# relay-monostable-multivib.net
KiCad netlist of a schematic drawn in EAGLE
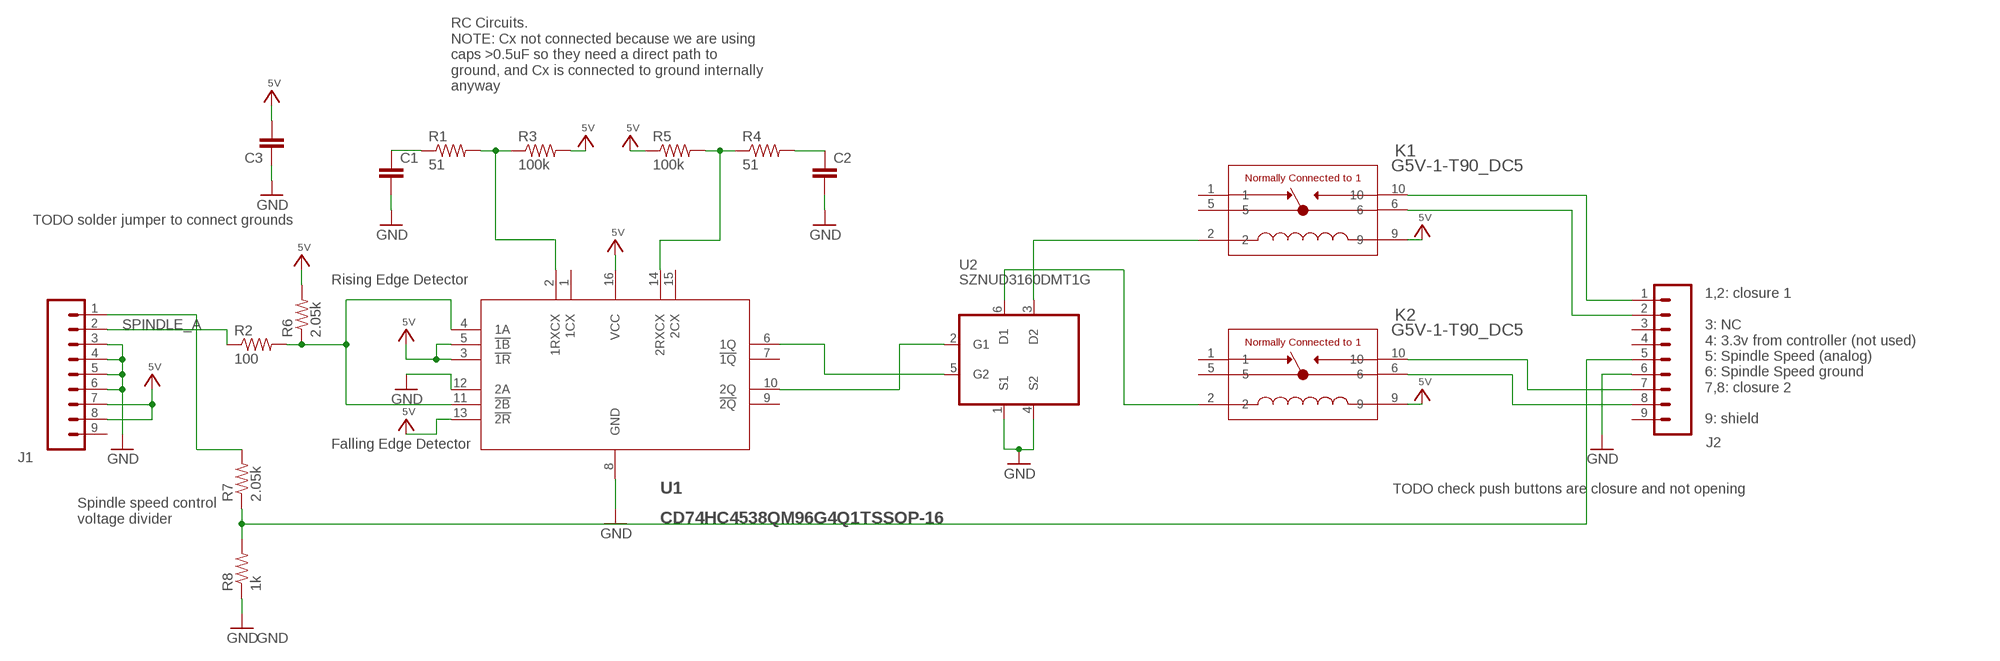
[diagram p0: schematic, sheet 1]

(export (version "E")
  (design (tool "Eeschema 10.0.6"))
  (components
    (comp (ref "C1")
      (value "C-EU1206-A")
      (footprint "eagle-import:1206-A")
      (libsource (lib "eagle-import") (part "C-EU1206-A"))
    )
    (comp (ref "C2")
      (value "C-EU1206-A")
      (footprint "eagle-import:1206-A")
      (libsource (lib "eagle-import") (part "C-EU1206-A"))
    )
    (comp (ref "C3")
      (value "C-EU1206-A")
      (footprint "eagle-import:1206-A")
      (libsource (lib "eagle-import") (part "C-EU1206-A"))
    )
    (comp (ref "J1")
      (value "CONN_09LONGPADS")
      (footprint "eagle-import:1X09_LONGPADS")
      (libsource (lib "eagle-import") (part "CONN_09LONGPADS"))
    )
    (comp (ref "J2")
      (value "CONN_09LONGPADS")
      (footprint "eagle-import:1X09_LONGPADS")
      (libsource (lib "eagle-import") (part "CONN_09LONGPADS"))
    )
    (comp (ref "K1")
      (value "G5V-1-T90_DC5")
      (footprint "eagle-import:RELAY_G5V-1_OMR")
      (fields
        (field (name "MANUFACTURER_PART_NUMBER") "G5V-1-T90 DC5")
        (field (name "COPYRIGHT") "Copyright (C) 2018 Accelerated Designs. All rights reserved")
      )
      (libsource (lib "eagle-import") (part "G5V-1-T90_DC5"))
    )
    (comp (ref "K2")
      (value "G5V-1-T90_DC5")
      (footprint "eagle-import:RELAY_G5V-1_OMR")
      (fields
        (field (name "MANUFACTURER_PART_NUMBER") "G5V-1-T90 DC5")
        (field (name "COPYRIGHT") "Copyright (C) 2018 Accelerated Designs. All rights reserved")
      )
      (libsource (lib "eagle-import") (part "G5V-1-T90_DC5"))
    )
    (comp (ref "R1")
      (value "51")
      (footprint "eagle-import:1206-A")
      (libsource (lib "eagle-import") (part "R-US_1206-A"))
    )
    (comp (ref "R2")
      (value "100")
      (footprint "eagle-import:1206-A")
      (libsource (lib "eagle-import") (part "R-US_1206-A"))
    )
    (comp (ref "R3")
      (value "100k")
      (footprint "eagle-import:1206-A")
      (libsource (lib "eagle-import") (part "R-US_1206-A"))
    )
    (comp (ref "R4")
      (value "51")
      (footprint "eagle-import:1206-A")
      (libsource (lib "eagle-import") (part "R-US_1206-A"))
    )
    (comp (ref "R5")
      (value "100k")
      (footprint "eagle-import:1206-A")
      (libsource (lib "eagle-import") (part "R-US_1206-A"))
    )
    (comp (ref "R6")
      (value "2.05k")
      (footprint "eagle-import:1206-A")
      (libsource (lib "eagle-import") (part "R-US_1206-A"))
    )
    (comp (ref "R7")
      (value "2.05k")
      (footprint "eagle-import:1206-A")
      (libsource (lib "eagle-import") (part "R-US_1206-A"))
    )
    (comp (ref "R8")
      (value "1k")
      (footprint "eagle-import:1206-A")
      (libsource (lib "eagle-import") (part "R-US_1206-A"))
    )
    (comp (ref "U1")
      (value "CD74HC4538QM96G4Q1TSSOP-16")
      (footprint "eagle-import:TSSOP16")
      (libsource (lib "eagle-import") (part "CD74HC4538QM96G4Q1TSSOP-16"))
    )
    (comp (ref "U2")
      (value "SZNUD3160DMT1G")
      (footprint "eagle-import:SC74_6")
      (libsource (lib "eagle-import") (part "SZNUD3160DMT1G"))
    )
  )
  (nets
    (net (code "1") (name "/SPINDLE_A") (class "Default")
      (node (ref "J1") (pin "1") (pinfunction "1_1") (pintype "passive"))
      (node (ref "R7") (pin "2") (pinfunction "2_2") (pintype "passive"))
    )
    (net (code "2") (name "5V") (class "Default")
      (node (ref "C3") (pin "2") (pinfunction "2_2") (pintype "passive"))
      (node (ref "J1") (pin "7") (pinfunction "7_7") (pintype "passive"))
      (node (ref "J1") (pin "8") (pinfunction "8_8") (pintype "passive"))
      (node (ref "K1") (pin "9") (pinfunction "9_9") (pintype "passive"))
      (node (ref "K2") (pin "9") (pinfunction "9_9") (pintype "passive"))
      (node (ref "R3") (pin "2") (pinfunction "2_2") (pintype "passive"))
      (node (ref "R5") (pin "1") (pinfunction "1_1") (pintype "passive"))
      (node (ref "R6") (pin "2") (pinfunction "2_2") (pintype "passive"))
      (node (ref "U1") (pin "13") (pinfunction "~{2R}_13") (pintype "input"))
      (node (ref "U1") (pin "16") (pinfunction "VCC_16") (pintype "power_in"))
      (node (ref "U1") (pin "3") (pinfunction "~{1R}_3") (pintype "input"))
      (node (ref "U1") (pin "5") (pinfunction "~{1B}_5") (pintype "input"))
    )
    (net (code "3") (name "GND") (class "Default")
      (node (ref "C1") (pin "2") (pinfunction "2_2") (pintype "passive"))
      (node (ref "C2") (pin "2") (pinfunction "2_2") (pintype "passive"))
      (node (ref "C3") (pin "1") (pinfunction "1_1") (pintype "passive"))
      (node (ref "J1") (pin "3") (pinfunction "3_3") (pintype "passive"))
      (node (ref "J1") (pin "4") (pinfunction "4_4") (pintype "passive"))
      (node (ref "J1") (pin "5") (pinfunction "5_5") (pintype "passive"))
      (node (ref "J1") (pin "6") (pinfunction "6_6") (pintype "passive"))
      (node (ref "J2") (pin "6") (pinfunction "6_6") (pintype "passive"))
      (node (ref "R8") (pin "1") (pinfunction "1_1") (pintype "passive"))
      (node (ref "U1") (pin "12") (pinfunction "2A_12") (pintype "input"))
      (node (ref "U1") (pin "8") (pinfunction "GND_8") (pintype "power_in"))
      (node (ref "U2") (pin "1") (pinfunction "S1_1") (pintype "power_in"))
      (node (ref "U2") (pin "4") (pinfunction "S2_4") (pintype "input"))
    )
    (net (code "4") (name "Net-(C1-Pad1)") (class "Default")
      (node (ref "C1") (pin "1") (pinfunction "1_1") (pintype "passive"))
      (node (ref "R1") (pin "1") (pinfunction "1_1") (pintype "passive"))
    )
    (net (code "5") (name "Net-(C2-Pad1)") (class "Default")
      (node (ref "C2") (pin "1") (pinfunction "1_1") (pintype "passive"))
      (node (ref "R4") (pin "2") (pinfunction "2_2") (pintype "passive"))
    )
    (net (code "6") (name "Net-(J1-Pad2)") (class "Default")
      (node (ref "J1") (pin "2") (pinfunction "2_2") (pintype "passive"))
      (node (ref "R2") (pin "1") (pinfunction "1_1") (pintype "passive"))
    )
    (net (code "7") (name "Net-(J2-Pad1)") (class "Default")
      (node (ref "J2") (pin "1") (pinfunction "1_1") (pintype "passive"))
      (node (ref "K1") (pin "10") (pinfunction "10_10") (pintype "passive"))
    )
    (net (code "8") (name "Net-(J2-Pad2)") (class "Default")
      (node (ref "J2") (pin "2") (pinfunction "2_2") (pintype "passive"))
      (node (ref "K1") (pin "6") (pinfunction "6_6") (pintype "passive"))
    )
    (net (code "9") (name "Net-(J2-Pad5)") (class "Default")
      (node (ref "J2") (pin "5") (pinfunction "5_5") (pintype "passive"))
      (node (ref "R7") (pin "1") (pinfunction "1_1") (pintype "passive"))
      (node (ref "R8") (pin "2") (pinfunction "2_2") (pintype "passive"))
    )
    (net (code "10") (name "Net-(J2-Pad7)") (class "Default")
      (node (ref "J2") (pin "7") (pinfunction "7_7") (pintype "passive"))
      (node (ref "K2") (pin "10") (pinfunction "10_10") (pintype "passive"))
    )
    (net (code "11") (name "Net-(J2-Pad8)") (class "Default")
      (node (ref "J2") (pin "8") (pinfunction "8_8") (pintype "passive"))
      (node (ref "K2") (pin "6") (pinfunction "6_6") (pintype "passive"))
    )
    (net (code "12") (name "Net-(U1-1A)") (class "Default")
      (node (ref "R2") (pin "2") (pinfunction "2_2") (pintype "passive"))
      (node (ref "R6") (pin "1") (pinfunction "1_1") (pintype "passive"))
      (node (ref "U1") (pin "11") (pinfunction "~{2B}_11") (pintype "input"))
      (node (ref "U1") (pin "4") (pinfunction "1A_4") (pintype "input"))
    )
    (net (code "13") (name "Net-(U1-1Q)") (class "Default")
      (node (ref "U1") (pin "6") (pinfunction "1Q_6") (pintype "output"))
      (node (ref "U2") (pin "5") (pinfunction "G2_5") (pintype "input"))
    )
    (net (code "14") (name "Net-(U1-1RXCX)") (class "Default")
      (node (ref "R1") (pin "2") (pinfunction "2_2") (pintype "passive"))
      (node (ref "R3") (pin "1") (pinfunction "1_1") (pintype "passive"))
      (node (ref "U1") (pin "2") (pinfunction "1RXCX_2") (pintype "passive"))
    )
    (net (code "15") (name "Net-(U1-2Q)") (class "Default")
      (node (ref "U1") (pin "10") (pinfunction "2Q_10") (pintype "output"))
      (node (ref "U2") (pin "2") (pinfunction "G1_2") (pintype "input"))
    )
    (net (code "16") (name "Net-(U1-2RXCX)") (class "Default")
      (node (ref "R4") (pin "1") (pinfunction "1_1") (pintype "passive"))
      (node (ref "R5") (pin "2") (pinfunction "2_2") (pintype "passive"))
      (node (ref "U1") (pin "14") (pinfunction "2RXCX_14") (pintype "passive"))
    )
    (net (code "17") (name "Net-(U2-D1)") (class "Default")
      (node (ref "K2") (pin "2") (pinfunction "2_2") (pintype "passive"))
      (node (ref "U2") (pin "6") (pinfunction "D1_6") (pintype "input"))
    )
    (net (code "18") (name "Net-(U2-D2)") (class "Default")
      (node (ref "K1") (pin "2") (pinfunction "2_2") (pintype "passive"))
      (node (ref "U2") (pin "3") (pinfunction "D2_3") (pintype "input"))
    )
    (net (code "19") (name "unconnected-(J1-Pad9)") (class "Default")
      (node (ref "J1") (pin "9") (pinfunction "9_9") (pintype "passive"))
    )
    (net (code "20") (name "unconnected-(J2-Pad3)") (class "Default")
      (node (ref "J2") (pin "3") (pinfunction "3_3") (pintype "passive"))
    )
    (net (code "21") (name "unconnected-(J2-Pad4)") (class "Default")
      (node (ref "J2") (pin "4") (pinfunction "4_4") (pintype "passive"))
    )
    (net (code "22") (name "unconnected-(J2-Pad9)") (class "Default")
      (node (ref "J2") (pin "9") (pinfunction "9_9") (pintype "passive"))
    )
    (net (code "23") (name "unconnected-(K1-Pad1)") (class "Default")
      (node (ref "K1") (pin "1") (pinfunction "1_1") (pintype "passive"))
    )
    (net (code "24") (name "unconnected-(K1-Pad5)") (class "Default")
      (node (ref "K1") (pin "5") (pinfunction "5_5") (pintype "passive"))
    )
    (net (code "25") (name "unconnected-(K2-Pad1)") (class "Default")
      (node (ref "K2") (pin "1") (pinfunction "1_1") (pintype "passive"))
    )
    (net (code "26") (name "unconnected-(K2-Pad5)") (class "Default")
      (node (ref "K2") (pin "5") (pinfunction "5_5") (pintype "passive"))
    )
    (net (code "27") (name "unconnected-(U1-1CX-Pad1)") (class "Default")
      (node (ref "U1") (pin "1") (pinfunction "1CX_1") (pintype "passive"))
    )
    (net (code "28") (name "unconnected-(U1-2CX-Pad15)") (class "Default")
      (node (ref "U1") (pin "15") (pinfunction "2CX_15") (pintype "passive"))
    )
    (net (code "29") (name "unconnected-(U1-~{1Q}-Pad7)") (class "Default")
      (node (ref "U1") (pin "7") (pinfunction "~{1Q}_7") (pintype "output"))
    )
    (net (code "30") (name "unconnected-(U1-~{2Q}-Pad9)") (class "Default")
      (node (ref "U1") (pin "9") (pinfunction "~{2Q}_9") (pintype "output"))
    )
  )
)
